# MRCS-Candlestick-Base.net
KiCad netlist of a schematic drawn in EAGLE
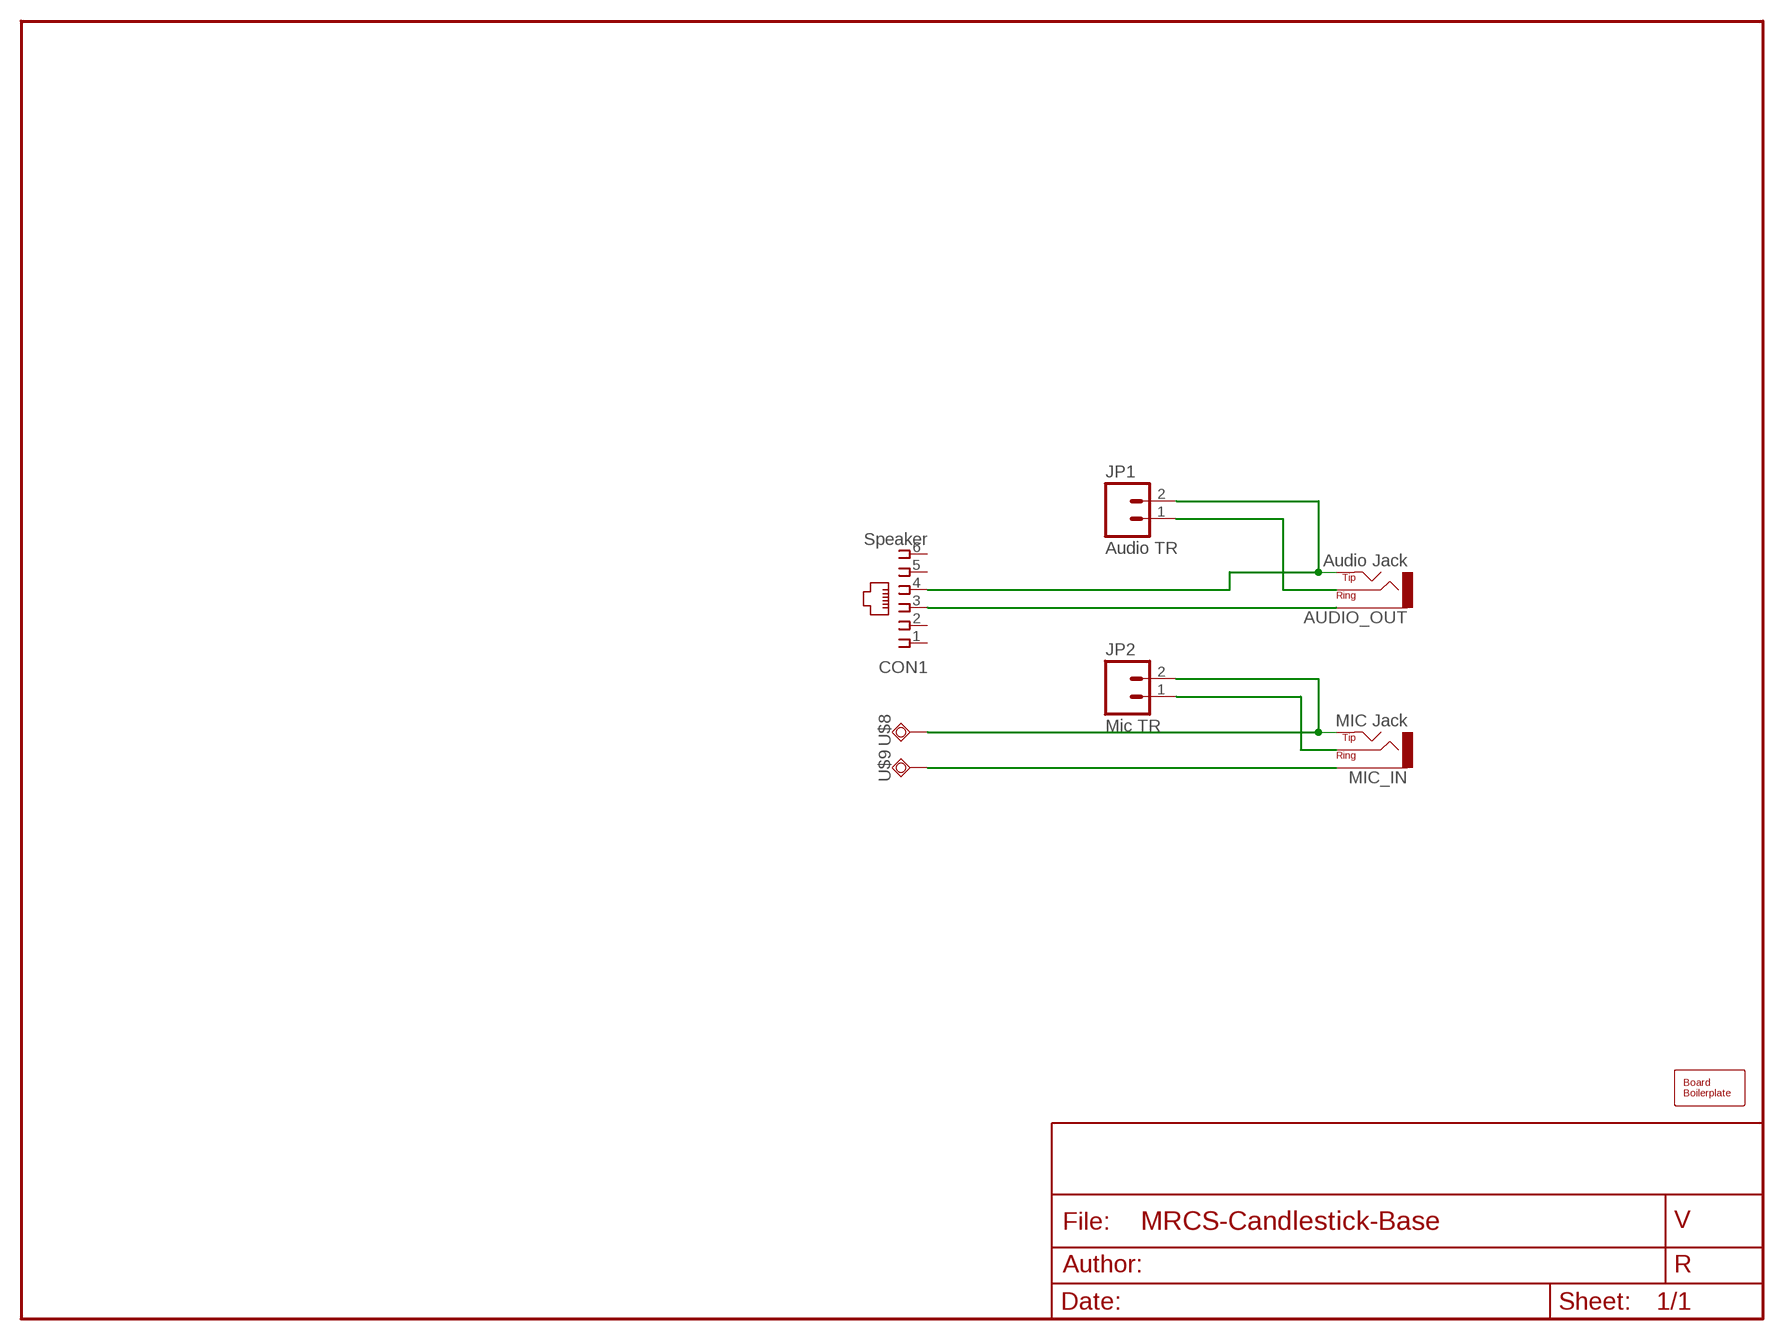
[diagram p0: schematic, sheet 1]

(export (version "E")
  (design (tool "Eeschema 10.0.6"))
  (components
    (comp (ref "AUDIO_OUT")
      (value "Audio Jack")
      (footprint "eagle-import:AUDIO-JACK-3.5MM_STEREO")
      (libsource (lib "eagle-import") (part "CONNECTOR-AUDIO3.5MM-ADAMTECH"))
    )
    (comp (ref "BOARD1")
      (value "BOARD69X50")
      (footprint "eagle-import:BOARD-DINRAIL-2.7IN-5CM")
      (libsource (lib "eagle-import") (part "BOARD69X50"))
    )
    (comp (ref "CON1")
      (value "Speaker")
      (footprint "eagle-import:RJ25-INVERTED")
      (libsource (lib "eagle-import") (part "CONNECTOR-RJ25-43860-2-MOLEX"))
    )
    (comp (ref "JP1")
      (value "Audio TR")
      (footprint "eagle-import:MOLEX-1X2_LOCK")
      (libsource (lib "eagle-import") (part "CONNECTOR-M02MOLEX-1X02-LOCK"))
    )
    (comp (ref "JP2")
      (value "Mic TR")
      (footprint "eagle-import:MOLEX-1X2_LOCK")
      (libsource (lib "eagle-import") (part "CONNECTOR-M02MOLEX-1X02-LOCK"))
    )
    (comp (ref "MIC_IN")
      (value "MIC Jack")
      (footprint "eagle-import:AUDIO-JACK-3.5MM_STEREO")
      (libsource (lib "eagle-import") (part "CONNECTOR-AUDIO3.5MM-ADAMTECH"))
    )
    (comp (ref "U$8")
      (value "SPADELUG.4")
      (footprint "eagle-import:SPADELUGPAD")
      (libsource (lib "eagle-import") (part "SPADELUG.4"))
    )
    (comp (ref "U$9")
      (value "SPADELUG.4")
      (footprint "eagle-import:SPADELUGPAD")
      (libsource (lib "eagle-import") (part "SPADELUG.4"))
    )
  )
  (nets
    (net (code "1") (name "Net-(AUDIO_OUT-SLEEVE)") (class "Default")
      (node (ref "AUDIO_OUT") (pin "GND") (pinfunction "SLEEVE_GND") (pintype "bidirectional"))
      (node (ref "CON1") (pin "3") (pinfunction "3_3") (pintype "passive"))
    )
    (net (code "2") (name "Net-(JP1-A)") (class "Default")
      (node (ref "AUDIO_OUT") (pin "RING") (pinfunction "RING_RING") (pintype "bidirectional"))
      (node (ref "JP1") (pin "1") (pinfunction "A_1") (pintype "passive"))
    )
    (net (code "3") (name "Net-(JP1-B)") (class "Default")
      (node (ref "AUDIO_OUT") (pin "TIP") (pinfunction "TIP_TIP") (pintype "bidirectional"))
      (node (ref "CON1") (pin "4") (pinfunction "4_4") (pintype "passive"))
      (node (ref "JP1") (pin "2") (pinfunction "B_2") (pintype "passive"))
    )
    (net (code "4") (name "Net-(JP2-A)") (class "Default")
      (node (ref "JP2") (pin "1") (pinfunction "A_1") (pintype "passive"))
      (node (ref "MIC_IN") (pin "RING") (pinfunction "RING_RING") (pintype "bidirectional"))
    )
    (net (code "5") (name "Net-(JP2-B)") (class "Default")
      (node (ref "JP2") (pin "2") (pinfunction "B_2") (pintype "passive"))
      (node (ref "MIC_IN") (pin "TIP") (pinfunction "TIP_TIP") (pintype "bidirectional"))
      (node (ref "U$8") (pin "P1") (pinfunction "TP_P1") (pintype "input"))
    )
    (net (code "6") (name "Net-(MIC_IN-SLEEVE)") (class "Default")
      (node (ref "MIC_IN") (pin "GND") (pinfunction "SLEEVE_GND") (pintype "bidirectional"))
      (node (ref "U$9") (pin "P1") (pinfunction "TP_P1") (pintype "input"))
    )
    (net (code "7") (name "unconnected-(CON1-Pad1)") (class "Default")
      (node (ref "CON1") (pin "1") (pinfunction "1_1") (pintype "passive"))
    )
    (net (code "8") (name "unconnected-(CON1-Pad2)") (class "Default")
      (node (ref "CON1") (pin "2") (pinfunction "2_2") (pintype "passive"))
    )
    (net (code "9") (name "unconnected-(CON1-Pad5)") (class "Default")
      (node (ref "CON1") (pin "5") (pinfunction "5_5") (pintype "passive"))
    )
    (net (code "10") (name "unconnected-(CON1-Pad6)") (class "Default")
      (node (ref "CON1") (pin "6") (pinfunction "6_6") (pintype "passive"))
    )
  )
)
